# cSLIM-SA-LoRa.net
KiCad netlist of a schematic drawn in Altium Designer
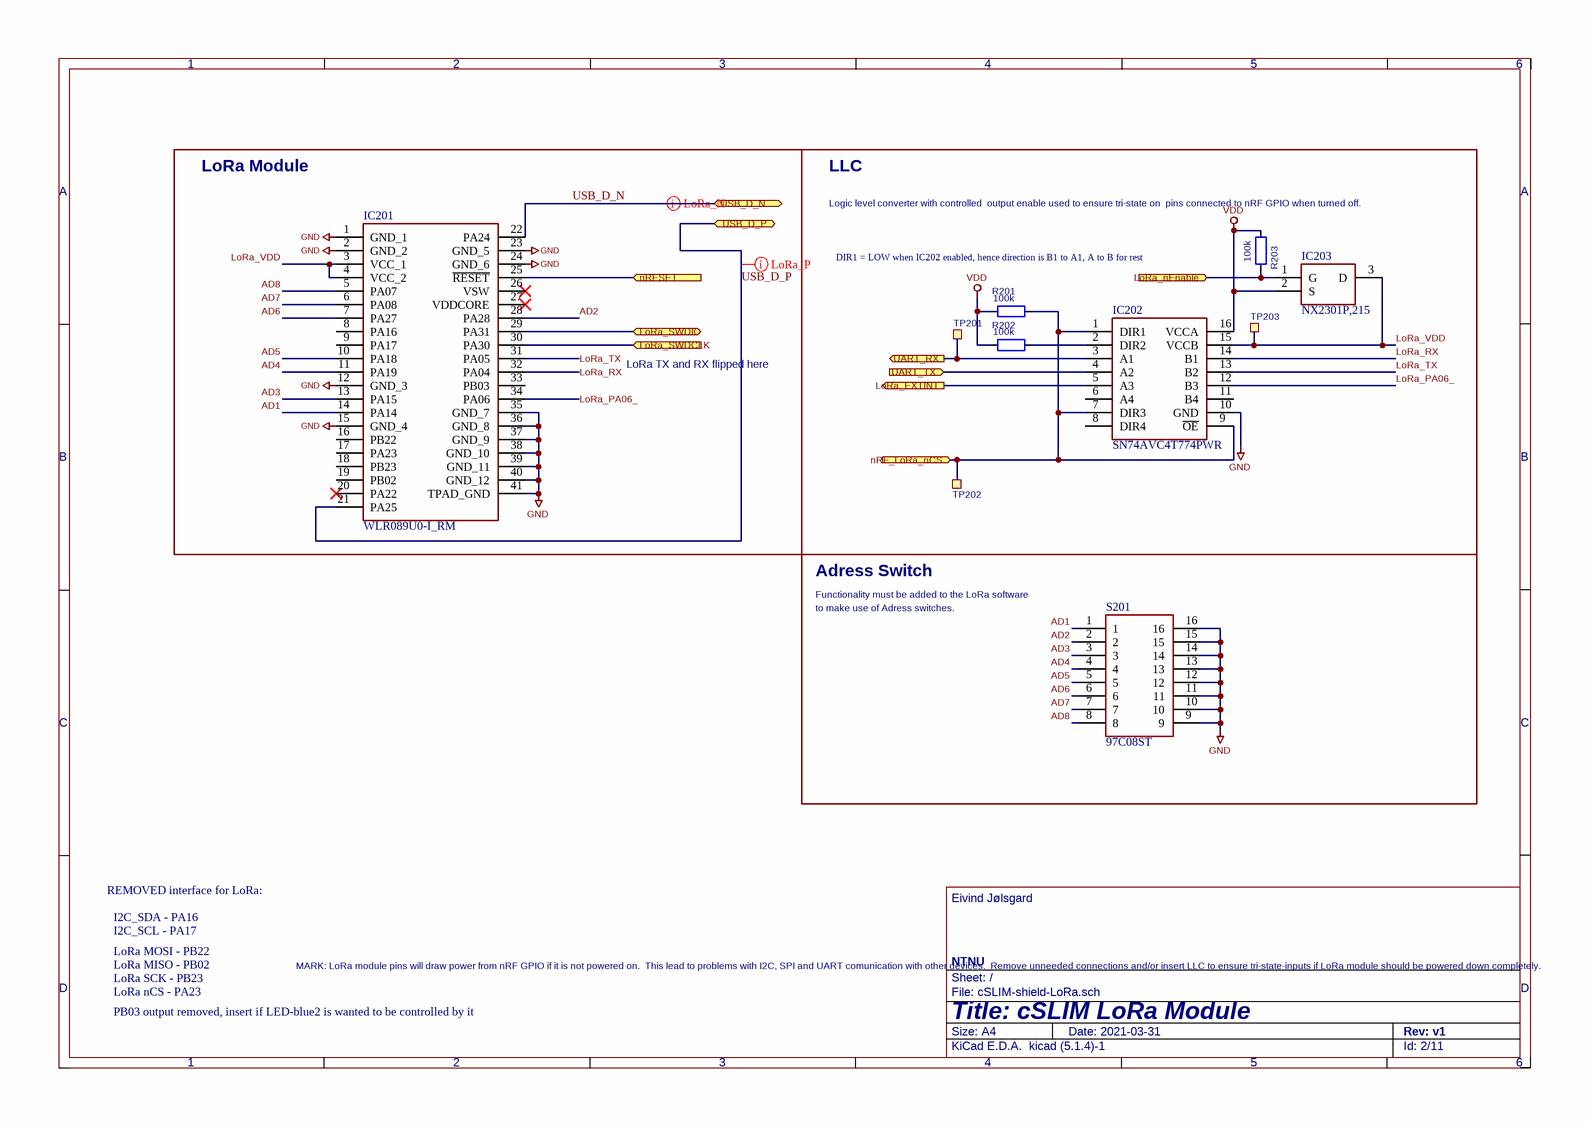
[diagram p0: cSLIM-SA-LoRa.SchDoc]

(export (version "E")
  (design (tool "Eeschema 10.0.6"))
  (components
    (comp (ref "IC201")
      (value "WLR089U0-I_RM")
      (footprint "cSLIM-SA:WLR089U0IRM")
      (description "Integrated Circuit")
      (fields
        (field (name "MANUFACTURER_PART_NUMBER") "WLR089U0-I/RM")
        (field (name "MOUSER PART NUMBER") "579-WLR089U0-I/RM")
      )
      (libsource (lib "cSLIM-SA") (part "WLR089U0-I_RM"))
    )
    (comp (ref "IC202")
      (value "SN74AVC4T774PWR")
      (footprint "cSLIM-SA:SOP65P640X120-16N")
      (description "Integrated Circuit")
      (fields (field (name "MOUSER PART NUMBER") "595-SN74AVC4T774PWR"))
      (libsource (lib "cSLIM-SA") (part "SN74AVC4T774PWR"))
    )
    (comp (ref "IC203")
      (value "NX2301P,215")
      (footprint "cSLIM-SA:SOT95P230X110-3N")
      (description "Integrated Circuit")
      (fields (field (name "MOUSER PART NUMBER") "771-NX2301P215"))
      (libsource (lib "cSLIM-SA") (part "NX2301P,215"))
    )
    (comp (ref "R201") (value "100k") (footprint "RESC1608X55N") (libsource (lib "") (part "R_1")))
    (comp (ref "R202") (value "100k") (footprint "RESC1608X55N") (libsource (lib "") (part "R_1")))
    (comp (ref "R203") (value "100k") (footprint "RESC1608X55N") (libsource (lib "cSLIM-SA") (part "R")))
    (comp (ref "S201")
      (value "97C08ST")
      (footprint "cSLIM-SA:SOIC127P671X170-16N")
      (description "Switch")
      (fields (field (name "MOUSER PART NUMBER") "706-97C08ST"))
      (libsource (lib "cSLIM-SA") (part "97C08ST"))
    )
    (comp (ref "TP201") (value "~") (footprint "cSLIM-SA:TP_SMD_Ø1.0mm") (libsource (lib "") (part "TP_1")))
    (comp (ref "TP202")
      (value "~")
      (footprint "cSLIM-SA:TP_SMD_Ø1.0mm")
      (libsource (lib "cSLIM-SA") (part "TP"))
    )
    (comp (ref "TP203") (value "~") (footprint "cSLIM-SA:TP_SMD_Ø1.0mm") (libsource (lib "") (part "TP_1")))
  )
  (nets
    (net (code "1") (name "/AD1") (class "Default")
      (node (ref "IC201") (pin "14") (pinfunction "PA14_14") (pintype "passive"))
      (node (ref "S201") (pin "1") (pinfunction "1_1") (pintype "passive"))
    )
    (net (code "2") (name "/AD2") (class "Default")
      (node (ref "IC201") (pin "28") (pinfunction "PA28_28") (pintype "passive"))
      (node (ref "S201") (pin "2") (pinfunction "2_2") (pintype "passive"))
    )
    (net (code "3") (name "/AD3") (class "Default")
      (node (ref "IC201") (pin "13") (pinfunction "PA15_13") (pintype "passive"))
      (node (ref "S201") (pin "3") (pinfunction "3_3") (pintype "passive"))
    )
    (net (code "4") (name "/AD4") (class "Default")
      (node (ref "IC201") (pin "11") (pinfunction "PA19_11") (pintype "passive"))
      (node (ref "S201") (pin "4") (pinfunction "4_4") (pintype "passive"))
    )
    (net (code "5") (name "/AD5") (class "Default")
      (node (ref "IC201") (pin "10") (pinfunction "PA18_10") (pintype "passive"))
      (node (ref "S201") (pin "5") (pinfunction "5_5") (pintype "passive"))
    )
    (net (code "6") (name "/AD6") (class "Default")
      (node (ref "IC201") (pin "7") (pinfunction "PA27_7") (pintype "passive"))
      (node (ref "S201") (pin "6") (pinfunction "6_6") (pintype "passive"))
    )
    (net (code "7") (name "/AD7") (class "Default")
      (node (ref "IC201") (pin "6") (pinfunction "PA08_6") (pintype "passive"))
      (node (ref "S201") (pin "7") (pinfunction "7_7") (pintype "passive"))
    )
    (net (code "8") (name "/AD8") (class "Default")
      (node (ref "IC201") (pin "5") (pinfunction "PA07_5") (pintype "passive"))
      (node (ref "S201") (pin "8") (pinfunction "8_8") (pintype "passive"))
    )
    (net (code "9") (name "/LoRa_EXTINT") (class "Default")
      (node (ref "IC202") (pin "5") (pinfunction "A3_5") (pintype "passive"))
    )
    (net (code "10") (name "/LoRa_PA06_") (class "Default")
      (node (ref "IC201") (pin "34") (pinfunction "PA06_34") (pintype "passive"))
      (node (ref "IC202") (pin "12") (pinfunction "B3_12") (pintype "passive"))
    )
    (net (code "11") (name "/LoRa_RX") (class "Default")
      (node (ref "IC201") (pin "32") (pinfunction "PA04_32") (pintype "passive"))
      (node (ref "IC202") (pin "14") (pinfunction "B1_14") (pintype "passive"))
    )
    (net (code "12") (name "/LoRa_SWDCLK") (class "Default")
      (node (ref "IC201") (pin "30") (pinfunction "PA30_30") (pintype "passive"))
    )
    (net (code "13") (name "/LoRa_SWDIO") (class "Default")
      (node (ref "IC201") (pin "29") (pinfunction "PA31_29") (pintype "passive"))
    )
    (net (code "14") (name "/LoRa_TX") (class "Default")
      (node (ref "IC201") (pin "31") (pinfunction "PA05_31") (pintype "passive"))
      (node (ref "IC202") (pin "13") (pinfunction "B2_13") (pintype "passive"))
    )
    (net (code "15") (name "/LoRa_VDD") (class "Default")
      (node (ref "IC201") (pin "3") (pinfunction "VCC_1_3") (pintype "passive"))
      (node (ref "IC201") (pin "4") (pinfunction "VCC_2_4") (pintype "passive"))
      (node (ref "IC202") (pin "15") (pinfunction "VCCB_15") (pintype "passive"))
      (node (ref "IC203") (pin "3") (pinfunction "D_3") (pintype "passive"))
      (node (ref "TP203") (pin "1") (pinfunction "1_1") (pintype "passive"))
    )
    (net (code "16") (name "/LoRa_nEnable") (class "Default")
      (node (ref "IC203") (pin "1") (pinfunction "G_1") (pintype "passive"))
      (node (ref "R203") (pin "1") (pinfunction "1_1") (pintype "passive"))
    )
    (net (code "17") (name "/UART_RX") (class "Default")
      (node (ref "IC202") (pin "3") (pinfunction "A1_3") (pintype "passive"))
      (node (ref "TP201") (pin "1") (pinfunction "1_1") (pintype "passive"))
    )
    (net (code "18") (name "/UART_TX") (class "Default")
      (node (ref "IC202") (pin "4") (pinfunction "A2_4") (pintype "passive"))
    )
    (net (code "19") (name "/USB_D_N") (class "Default")
      (node (ref "IC201") (pin "22") (pinfunction "PA24_22") (pintype "passive"))
    )
    (net (code "20") (name "/USB_D_P") (class "Default")
      (node (ref "IC201") (pin "21") (pinfunction "PA25_21") (pintype "passive"))
    )
    (net (code "21") (name "/nRESET") (class "Default")
      (node (ref "IC201") (pin "25") (pinfunction "~{RESET}_25") (pintype "passive"))
    )
    (net (code "22") (name "/nRF_LoRa_nCS") (class "Default")
      (node (ref "IC202") (pin "1") (pinfunction "DIR1_1") (pintype "passive"))
      (node (ref "IC202") (pin "7") (pinfunction "DIR3_7") (pintype "passive"))
      (node (ref "IC202") (pin "9") (pinfunction "~{OE}_9") (pintype "passive"))
      (node (ref "R201") (pin "1") (pinfunction "1_1") (pintype "passive"))
      (node (ref "TP202") (pin "1") (pinfunction "1_1") (pintype "passive"))
    )
    (net (code "23") (name "GND") (class "Default")
      (node (ref "IC201") (pin "1") (pinfunction "GND_1_1") (pintype "passive"))
      (node (ref "IC201") (pin "12") (pinfunction "GND_3_12") (pintype "passive"))
      (node (ref "IC201") (pin "15") (pinfunction "GND_4_15") (pintype "passive"))
      (node (ref "IC201") (pin "2") (pinfunction "GND_2_2") (pintype "passive"))
      (node (ref "IC201") (pin "23") (pinfunction "GND_5_23") (pintype "passive"))
      (node (ref "IC201") (pin "24") (pinfunction "GND_6_24") (pintype "passive"))
      (node (ref "IC201") (pin "35") (pinfunction "GND_7_35") (pintype "passive"))
      (node (ref "IC201") (pin "36") (pinfunction "GND_8_36") (pintype "passive"))
      (node (ref "IC201") (pin "37") (pinfunction "GND_9_37") (pintype "passive"))
      (node (ref "IC201") (pin "38") (pinfunction "GND_10_38") (pintype "passive"))
      (node (ref "IC201") (pin "39") (pinfunction "GND_11_39") (pintype "passive"))
      (node (ref "IC201") (pin "40") (pinfunction "GND_12_40") (pintype "passive"))
      (node (ref "IC201") (pin "41") (pinfunction "TPAD_GND_41") (pintype "passive"))
      (node (ref "IC202") (pin "10") (pinfunction "GND_10") (pintype "passive"))
      (node (ref "S201") (pin "10") (pinfunction "10_10") (pintype "passive"))
      (node (ref "S201") (pin "11") (pinfunction "11_11") (pintype "passive"))
      (node (ref "S201") (pin "12") (pinfunction "12_12") (pintype "passive"))
      (node (ref "S201") (pin "13") (pinfunction "13_13") (pintype "passive"))
      (node (ref "S201") (pin "14") (pinfunction "14_14") (pintype "passive"))
      (node (ref "S201") (pin "15") (pinfunction "15_15") (pintype "passive"))
      (node (ref "S201") (pin "16") (pinfunction "16_16") (pintype "passive"))
      (node (ref "S201") (pin "9") (pinfunction "9_9") (pintype "passive"))
    )
    (net (code "24") (name "Net-(IC202-DIR2)") (class "Default")
      (node (ref "IC202") (pin "2") (pinfunction "DIR2_2") (pintype "passive"))
      (node (ref "R202") (pin "1") (pinfunction "1_1") (pintype "passive"))
    )
    (net (code "25") (name "VDD") (class "Default")
      (node (ref "IC202") (pin "16") (pinfunction "VCCA_16") (pintype "passive"))
      (node (ref "IC203") (pin "2") (pinfunction "S_2") (pintype "passive"))
      (node (ref "R201") (pin "2") (pinfunction "2_2") (pintype "passive"))
      (node (ref "R202") (pin "2") (pinfunction "2_2") (pintype "passive"))
      (node (ref "R203") (pin "2") (pinfunction "2_2") (pintype "passive"))
    )
    (net (code "26") (name "unconnected-(IC201-PA16-Pad8)") (class "Default")
      (node (ref "IC201") (pin "8") (pinfunction "PA16_8") (pintype "passive"))
    )
    (net (code "27") (name "unconnected-(IC201-PA17-Pad9)") (class "Default")
      (node (ref "IC201") (pin "9") (pinfunction "PA17_9") (pintype "passive"))
    )
    (net (code "28") (name "unconnected-(IC201-PA22-Pad20)") (class "Default")
      (node (ref "IC201") (pin "20") (pinfunction "PA22_20") (pintype "passive+no_connect"))
    )
    (net (code "29") (name "unconnected-(IC201-PA23-Pad17)") (class "Default")
      (node (ref "IC201") (pin "17") (pinfunction "PA23_17") (pintype "passive"))
    )
    (net (code "30") (name "unconnected-(IC201-PB02-Pad19)") (class "Default")
      (node (ref "IC201") (pin "19") (pinfunction "PB02_19") (pintype "passive"))
    )
    (net (code "31") (name "unconnected-(IC201-PB03-Pad33)") (class "Default")
      (node (ref "IC201") (pin "33") (pinfunction "PB03_33") (pintype "passive"))
    )
    (net (code "32") (name "unconnected-(IC201-PB22-Pad16)") (class "Default")
      (node (ref "IC201") (pin "16") (pinfunction "PB22_16") (pintype "passive"))
    )
    (net (code "33") (name "unconnected-(IC201-PB23-Pad18)") (class "Default")
      (node (ref "IC201") (pin "18") (pinfunction "PB23_18") (pintype "passive"))
    )
    (net (code "34") (name "unconnected-(IC201-VDDCORE-Pad27)") (class "Default")
      (node (ref "IC201") (pin "27") (pinfunction "VDDCORE_27") (pintype "passive+no_connect"))
    )
    (net (code "35") (name "unconnected-(IC201-VSW-Pad26)") (class "Default")
      (node (ref "IC201") (pin "26") (pinfunction "VSW_26") (pintype "passive+no_connect"))
    )
    (net (code "36") (name "unconnected-(IC202-A4-Pad6)") (class "Default")
      (node (ref "IC202") (pin "6") (pinfunction "A4_6") (pintype "passive"))
    )
    (net (code "37") (name "unconnected-(IC202-B4-Pad11)") (class "Default")
      (node (ref "IC202") (pin "11") (pinfunction "B4_11") (pintype "passive"))
    )
    (net (code "38") (name "unconnected-(IC202-DIR4-Pad8)") (class "Default")
      (node (ref "IC202") (pin "8") (pinfunction "DIR4_8") (pintype "passive"))
    )
  )
)
